# mainSheet.net
KiCad netlist of a schematic drawn in Altium Designer
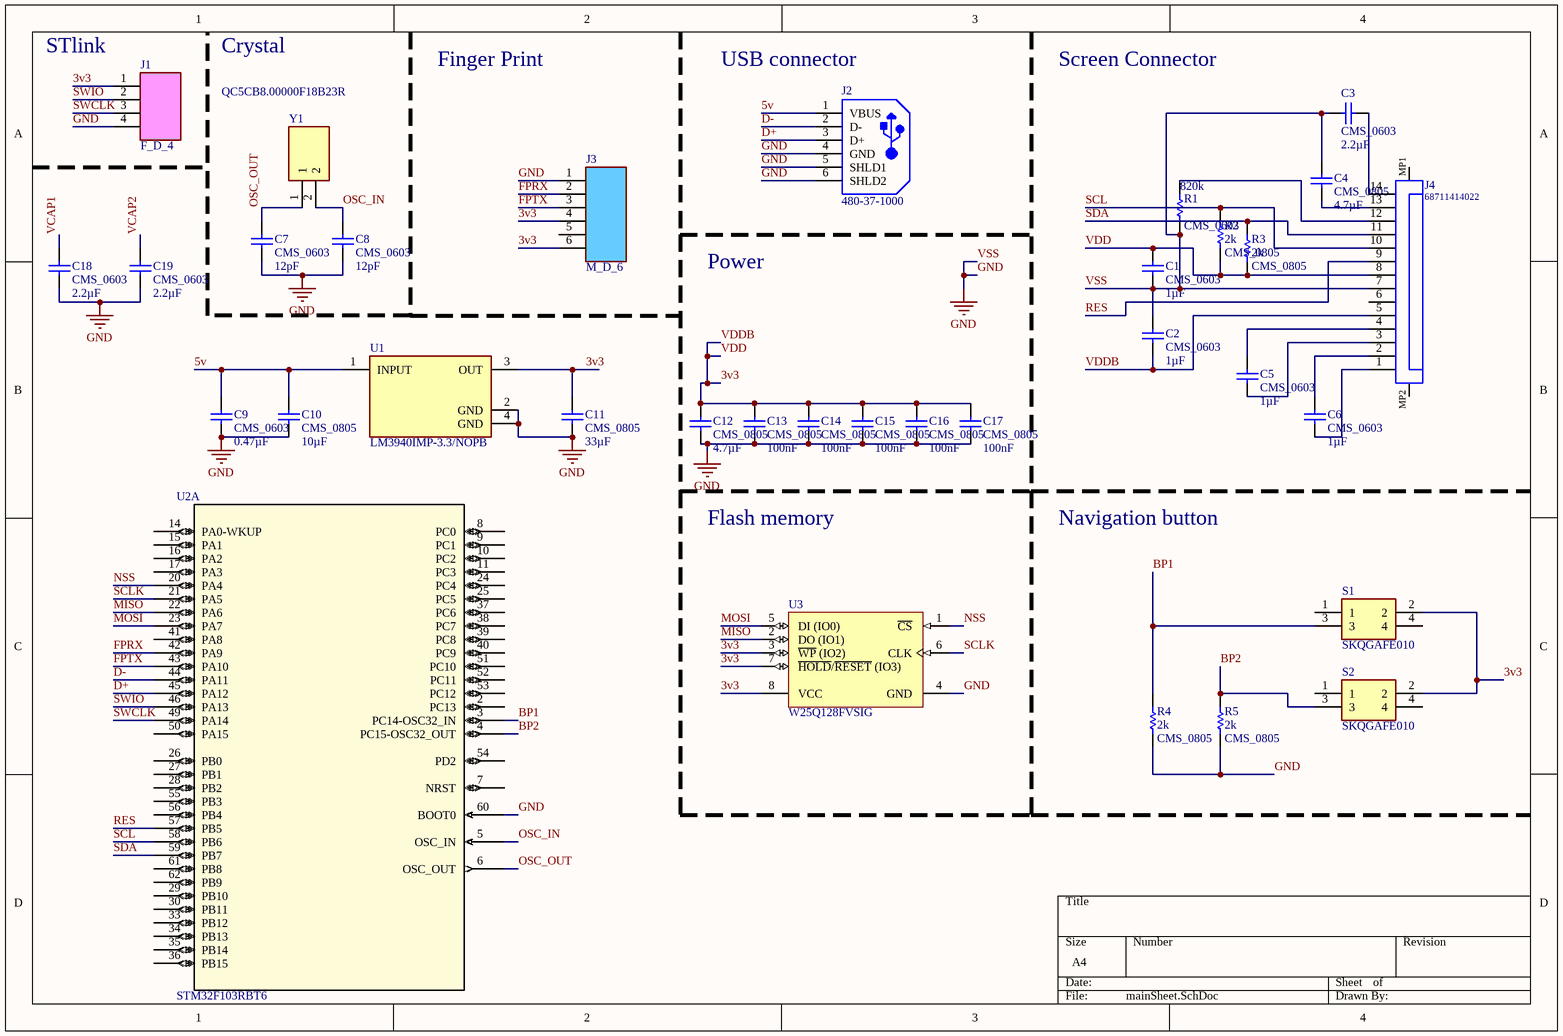
[diagram p0: mainSheet.SchDoc]

(export (version "E")
  (design (tool "Eeschema 10.0.6"))
  (components
    (comp (ref "C1")
      (value "CMS_0603")
      (footprint "CONDENSATEUR_CMS_0603")
      (description "CONDENSATEUR CMS CERAMIQUE 0603")
      (fields (field (name "TYPE") "CMS_0603") (field (name "CONDO") "1µF"))
      (libsource (lib "composants passifs") (part "CONDENSATEUR_CMS_CER_0603"))
    )
    (comp (ref "C2")
      (value "CMS_0603")
      (footprint "CONDENSATEUR_CMS_0603")
      (description "CONDENSATEUR CMS CERAMIQUE 0603")
      (fields (field (name "TYPE") "CMS_0603") (field (name "CONDO") "1µF"))
      (libsource (lib "composants passifs") (part "CONDENSATEUR_CMS_CER_0603"))
    )
    (comp (ref "C3")
      (value "CMS_0603")
      (footprint "CONDENSATEUR_CMS_0603")
      (description "CONDENSATEUR CMS CERAMIQUE 0603")
      (fields (field (name "TYPE") "CMS_0603") (field (name "CONDO") "2.2µF"))
      (libsource (lib "composants passifs") (part "CONDENSATEUR_CMS_CER_0603"))
    )
    (comp (ref "C4")
      (value "CMS_0805")
      (footprint "CONDENSATEUR_CMS_0805")
      (description "CONDENSATEUR CMS CERAMIQUE 0805")
      (fields (field (name "TYPE") "CMS_0805") (field (name "16V / X7R") "4.7µF"))
      (libsource (lib "composants passifs") (part "CONDENSATEUR_CMS_CER_0805"))
    )
    (comp (ref "C5")
      (value "CMS_0603")
      (footprint "CONDENSATEUR_CMS_0603")
      (description "CONDENSATEUR CMS CERAMIQUE 0603")
      (fields (field (name "TYPE") "CMS_0603") (field (name "16V X5R") "1µF"))
      (libsource (lib "composants passifs") (part "CONDENSATEUR_CMS_CER_0603"))
    )
    (comp (ref "C6")
      (value "CMS_0603")
      (footprint "CONDENSATEUR_CMS_0603")
      (description "CONDENSATEUR CMS CERAMIQUE 0603")
      (fields (field (name "TYPE") "CMS_0603") (field (name "16V X5R") "1µF"))
      (libsource (lib "composants passifs") (part "CONDENSATEUR_CMS_CER_0603"))
    )
    (comp (ref "C7")
      (value "CMS_0603")
      (footprint "CONDENSATEUR_CMS_0603")
      (description "CONDENSATEUR CMS CERAMIQUE 0603")
      (fields (field (name "TYPE") "CMS_0603") (field (name "CONDO") "12pF"))
      (libsource (lib "composants passifs") (part "CONDENSATEUR_CMS_CER_0603"))
    )
    (comp (ref "C8")
      (value "CMS_0603")
      (footprint "CONDENSATEUR_CMS_0603")
      (description "CONDENSATEUR CMS CERAMIQUE 0603")
      (fields (field (name "TYPE") "CMS_0603") (field (name "CONDO") "12pF"))
      (libsource (lib "composants passifs") (part "CONDENSATEUR_CMS_CER_0603"))
    )
    (comp (ref "C9")
      (value "CMS_0603")
      (footprint "CONDENSATEUR_CMS_0603")
      (description "CONDENSATEUR CMS CERAMIQUE 0603")
      (fields (field (name "TYPE") "CMS_0603") (field (name "CONDO") "0.47µF"))
      (libsource (lib "composants passifs") (part "CONDENSATEUR_CMS_CER_0603"))
    )
    (comp (ref "C10")
      (value "10µF")
      (footprint "CONDENSATEUR_CMS_0805")
      (description "CONDENSATEUR CMS CERAMIQUE 0805")
      (fields (field (name "TYPE") "CMS_0805") (field (name "Comment") "CMS_0805"))
      (libsource (lib "composants passifs") (part "CONDENSATEUR_CMS_CER_0805"))
    )
    (comp (ref "C11")
      (value "33µF")
      (footprint "CONDENSATEUR_CMS_0805")
      (description "CONDENSATEUR CMS CERAMIQUE 0805")
      (fields (field (name "TYPE") "CMS_0805") (field (name "Comment") "CMS_0805"))
      (libsource (lib "composants passifs") (part "CONDENSATEUR_CMS_CER_0805"))
    )
    (comp (ref "C12")
      (value "CMS_0805")
      (footprint "CONDENSATEUR_CMS_0805")
      (description "CONDENSATEUR CMS CERAMIQUE 0805")
      (fields (field (name "TYPE") "CMS_0805") (field (name "16V / X7R") "4.7µF"))
      (libsource (lib "composants passifs") (part "CONDENSATEUR_CMS_CER_0805"))
    )
    (comp (ref "C13")
      (value "100nF")
      (footprint "CONDENSATEUR_CMS_0805")
      (description "CONDENSATEUR CMS CERAMIQUE 0805")
      (fields (field (name "TYPE") "CMS_0805") (field (name "Comment") "CMS_0805"))
      (libsource (lib "composants passifs") (part "CONDENSATEUR_CMS_CER_0805"))
    )
    (comp (ref "C14")
      (value "100nF")
      (footprint "CONDENSATEUR_CMS_0805")
      (description "CONDENSATEUR CMS CERAMIQUE 0805")
      (fields (field (name "TYPE") "CMS_0805") (field (name "Comment") "CMS_0805"))
      (libsource (lib "composants passifs") (part "CONDENSATEUR_CMS_CER_0805"))
    )
    (comp (ref "C15")
      (value "100nF")
      (footprint "CONDENSATEUR_CMS_0805")
      (description "CONDENSATEUR CMS CERAMIQUE 0805")
      (fields (field (name "TYPE") "CMS_0805") (field (name "Comment") "CMS_0805"))
      (libsource (lib "composants passifs") (part "CONDENSATEUR_CMS_CER_0805"))
    )
    (comp (ref "C16")
      (value "100nF")
      (footprint "CONDENSATEUR_CMS_0805")
      (description "CONDENSATEUR CMS CERAMIQUE 0805")
      (fields (field (name "TYPE") "CMS_0805") (field (name "Comment") "CMS_0805"))
      (libsource (lib "composants passifs") (part "CONDENSATEUR_CMS_CER_0805"))
    )
    (comp (ref "C17")
      (value "100nF")
      (footprint "CONDENSATEUR_CMS_0805")
      (description "CONDENSATEUR CMS CERAMIQUE 0805")
      (fields (field (name "TYPE") "CMS_0805") (field (name "Comment") "CMS_0805"))
      (libsource (lib "composants passifs") (part "CONDENSATEUR_CMS_CER_0805"))
    )
    (comp (ref "C18")
      (value "CMS_0603")
      (footprint "CONDENSATEUR_CMS_0603")
      (description "CONDENSATEUR CMS CERAMIQUE 0603")
      (fields (field (name "TYPE") "CMS_0603") (field (name "CONDO") "2.2µF"))
      (libsource (lib "composants passifs") (part "CONDENSATEUR_CMS_CER_0603"))
    )
    (comp (ref "C19")
      (value "CMS_0603")
      (footprint "CONDENSATEUR_CMS_0603")
      (description "CONDENSATEUR CMS CERAMIQUE 0603")
      (fields (field (name "TYPE") "CMS_0603") (field (name "CONDO") "2.2µF"))
      (libsource (lib "composants passifs") (part "CONDENSATEUR_CMS_CER_0603"))
    )
    (comp (ref "J1")
      (value "BARRETTE_4 CONTACTS_1 RANGEE_FEMELLE_DROITE")
      (footprint "BARRETTE_4_F_D")
      (description "BARRETTE 4 CONTACTS 1 RANGEE FEMELLE DROITE")
      (fields (field (name "TYPE") "F_D_4"))
      (libsource (lib "connecteurs") (part "BARRETTE_4 CONTACTS_1 RANGEE_FEMELLE_DROITE"))
    )
    (comp (ref "J2")
      (value "480-37-1000")
      (footprint "MOLX-480-37-1000_V")
      (fields (field (name "TOLERANCE") "1%"))
      (libsource (lib "Components - 04.06.22 - 23.53") (part "CMP-1676-00005-1"))
    )
    (comp (ref "J3")
      (value "BARRETTE_6 CONTACTS_1 RANGEE_MALE_DROITE")
      (footprint "BARRETTE_6_M_D")
      (description "BARRETTE 6 CONTACTS 1 RANGEE MALE DROITE")
      (fields (field (name "TYPE") "M_D_6"))
      (libsource (lib "connecteurs") (part "BARRETTE_6 CONTACTS_1 RANGEE_MALE_DROITE"))
    )
    (comp (ref "J4")
      (value "68711414022")
      (footprint "68711414022")
      (description "SMT ZIF Connectors WR-FPC, Horizontal, Top Contact, pitch 0.5 mm, 14 pins")
      (fields (field (name "MANUFACTURER") "Wurth Elektronik") (field (name "PUBLISHER") "WurthElektronik"))
      (libsource (lib "Components - 04.06.22 - 18.37") (part "CMP-1502-01553-1"))
    )
    (comp (ref "R1")
      (value "820k")
      (footprint "RESISTANCE_CMS_0603")
      (description "RESISTANCE CMS 0603")
      (fields (field (name "TYPE") "CMS_0603") (field (name "Comment") "RESISTANCE_CMS_0603"))
      (libsource (lib "composants passifs") (part "RESISTANCE_CMS_0603"))
    )
    (comp (ref "R2")
      (value "2k")
      (footprint "RESISTANCE_CMS_0805")
      (description "RESISTANCE CMS 0805")
      (fields (field (name "TYPE") "CMS_0805") (field (name "Comment") "RESISTANCE_CMS_0805"))
      (libsource (lib "composants passifs") (part "RESISTANCE_CMS_0805"))
    )
    (comp (ref "R3")
      (value "2k")
      (footprint "RESISTANCE_CMS_0805")
      (description "RESISTANCE CMS 0805")
      (fields (field (name "TYPE") "CMS_0805") (field (name "Comment") "RESISTANCE_CMS_0805"))
      (libsource (lib "composants passifs") (part "RESISTANCE_CMS_0805"))
    )
    (comp (ref "R4")
      (value "2k")
      (footprint "RESISTANCE_CMS_0805")
      (description "RESISTANCE CMS 0805")
      (fields (field (name "TYPE") "CMS_0805") (field (name "Comment") "RESISTANCE_CMS_0805"))
      (libsource (lib "composants passifs") (part "RESISTANCE_CMS_0805"))
    )
    (comp (ref "R5")
      (value "2k")
      (footprint "RESISTANCE_CMS_0805")
      (description "RESISTANCE CMS 0805")
      (fields (field (name "TYPE") "CMS_0805") (field (name "Comment") "RESISTANCE_CMS_0805"))
      (libsource (lib "composants passifs") (part "RESISTANCE_CMS_0805"))
    )
    (comp (ref "S1")
      (value "SKQGAFE010")
      (footprint "SamacSys:SKQGAKE010")
      (description "Switch")
      (fields (field (name "RS PART NUMBER") "7582060P"))
      (libsource (lib "*") (part "SKQGAFE010"))
    )
    (comp (ref "S2")
      (value "SKQGAFE010")
      (footprint "SamacSys:SKQGAKE010")
      (description "Switch")
      (fields (field (name "RS PART NUMBER") "7582060P"))
      (libsource (lib "*") (part "SKQGAFE010"))
    )
    (comp (ref "U1")
      (value "LM3940IMP-3.3/NOPB")
      (footprint "FP-DCY0004A-IPC_C")
      (description "IC REG LINEAR 3.3V 1A SOT223-4")
      (libsource (lib "Components - 07.06.22 - 09.42") (part "CMP-0062-01788-4"))
    )
    (comp (ref "U2")
      (value "STM32F103RBT6")
      (footprint "LQFP64-10x10mm")
      (description "No Description Available")
      (fields (field (name "COPYRIGHT") "Copyright (C) 2022 Ultra Librarian. All rights reserved."))
      (libsource (lib "STM32F103RBT6") (part "STM32F103RBT6"))
    )
    (comp (ref "U3")
      (value "W25Q128FVSIG")
      (footprint "WINB-SOIC-8_N")
      (fields (field (name "MANUFACTURER") "Winbond"))
      (libsource (lib "Components - 04.06.22 - 23.40") (part "CMP-2000-05005-1"))
    )
    (comp (ref "Y1")
      (value "QC5CB8.00000F18B23R")
      (footprint "SamacSys:QC5CB")
      (description "Crystal or Oscillator")
      (fields (field (name "RS PART NUMBER") "8136093P"))
      (libsource (lib "*") (part "QC5CB8.00000F18B23R"))
    )
  )
  (nets
    (net (code "1") (name "/3v3") (class "Default")
      (node (ref "C1") (pin "2") (pinfunction "2_2") (pintype "passive"))
      (node (ref "C11") (pin "2") (pinfunction "2_2") (pintype "passive"))
      (node (ref "C12") (pin "1") (pinfunction "1_1") (pintype "passive"))
      (node (ref "C13") (pin "2") (pinfunction "2_2") (pintype "passive"))
      (node (ref "C14") (pin "2") (pinfunction "2_2") (pintype "passive"))
      (node (ref "C15") (pin "2") (pinfunction "2_2") (pintype "passive"))
      (node (ref "C16") (pin "2") (pinfunction "2_2") (pintype "passive"))
      (node (ref "C17") (pin "2") (pinfunction "2_2") (pintype "passive"))
      (node (ref "C2") (pin "1") (pinfunction "1_1") (pintype "passive"))
      (node (ref "J1") (pin "1") (pinfunction "1_1") (pintype "passive"))
      (node (ref "J3") (pin "4") (pinfunction "4_4") (pintype "passive"))
      (node (ref "J3") (pin "6") (pinfunction "6_6") (pintype "passive"))
      (node (ref "J4") (pin "5") (pinfunction "5_5") (pintype "passive"))
      (node (ref "J4") (pin "8") (pinfunction "8_8") (pintype "passive"))
      (node (ref "R2") (pin "1") (pinfunction "1_1") (pintype "passive"))
      (node (ref "R3") (pin "1") (pinfunction "1_1") (pintype "passive"))
      (node (ref "S1") (pin "2") (pinfunction "2_2") (pintype "passive"))
      (node (ref "S2") (pin "2") (pinfunction "2_2") (pintype "passive"))
      (node (ref "U1") (pin "3") (pinfunction "OUT_3") (pintype "power_in"))
      (node (ref "U3") (pin "3") (pinfunction "~{WP}_(IO2)_3") (pintype "bidirectional"))
      (node (ref "U3") (pin "7") (pinfunction "~{HOLD}/~{RESET}_(IO3)_7") (pintype "bidirectional"))
      (node (ref "U3") (pin "8") (pinfunction "VCC_8") (pintype "power_in"))
    )
    (net (code "2") (name "/5v") (class "Default")
      (node (ref "C10") (pin "2") (pinfunction "2_2") (pintype "passive"))
      (node (ref "C9") (pin "2") (pinfunction "2_2") (pintype "passive"))
      (node (ref "J2") (pin "1") (pinfunction "VBUS_1") (pintype "passive"))
      (node (ref "U1") (pin "1") (pinfunction "INPUT_1") (pintype "power_in"))
    )
    (net (code "3") (name "/BP1") (class "Default")
      (node (ref "R4") (pin "2") (pinfunction "2_2") (pintype "passive"))
      (node (ref "S1") (pin "3") (pinfunction "3_3") (pintype "passive"))
      (node (ref "U2") (pin "3") (pinfunction "PC14-OSC32_IN_3") (pintype "bidirectional"))
    )
    (net (code "4") (name "/BP2") (class "Default")
      (node (ref "R5") (pin "2") (pinfunction "2_2") (pintype "passive"))
      (node (ref "S2") (pin "3") (pinfunction "3_3") (pintype "passive"))
      (node (ref "U2") (pin "4") (pinfunction "PC15-OSC32_OUT_4") (pintype "bidirectional"))
    )
    (net (code "5") (name "/D+") (class "Default")
      (node (ref "J2") (pin "3") (pinfunction "D+_3") (pintype "passive"))
      (node (ref "U2") (pin "45") (pinfunction "PA12_45") (pintype "bidirectional"))
    )
    (net (code "6") (name "/D-") (class "Default")
      (node (ref "J2") (pin "2") (pinfunction "D-_2") (pintype "passive"))
      (node (ref "U2") (pin "44") (pinfunction "PA11_44") (pintype "bidirectional"))
    )
    (net (code "7") (name "/FPRX") (class "Default")
      (node (ref "J3") (pin "2") (pinfunction "2_2") (pintype "passive"))
      (node (ref "U2") (pin "42") (pinfunction "PA9_42") (pintype "bidirectional"))
    )
    (net (code "8") (name "/FPTX") (class "Default")
      (node (ref "J3") (pin "3") (pinfunction "3_3") (pintype "passive"))
      (node (ref "U2") (pin "43") (pinfunction "PA10_43") (pintype "bidirectional"))
    )
    (net (code "9") (name "/MISO") (class "Default")
      (node (ref "U2") (pin "22") (pinfunction "PA6_22") (pintype "bidirectional"))
      (node (ref "U3") (pin "2") (pinfunction "DO_(IO1)_2") (pintype "bidirectional"))
    )
    (net (code "10") (name "/MOSI") (class "Default")
      (node (ref "U2") (pin "23") (pinfunction "PA7_23") (pintype "bidirectional"))
      (node (ref "U3") (pin "5") (pinfunction "DI_(IO0)_5") (pintype "bidirectional"))
    )
    (net (code "11") (name "/NSS") (class "Default")
      (node (ref "U2") (pin "20") (pinfunction "PA4_20") (pintype "bidirectional"))
      (node (ref "U3") (pin "1") (pinfunction "~{CS}_1") (pintype "input"))
    )
    (net (code "12") (name "/OSC_IN") (class "Default")
      (node (ref "C8") (pin "2") (pinfunction "2_2") (pintype "passive"))
      (node (ref "U2") (pin "5") (pinfunction "OSC_IN_5") (pintype "input"))
      (node (ref "Y1") (pin "2") (pinfunction "2_2") (pintype "passive"))
    )
    (net (code "13") (name "/OSC_OUT") (class "Default")
      (node (ref "C7") (pin "2") (pinfunction "2_2") (pintype "passive"))
      (node (ref "U2") (pin "6") (pinfunction "OSC_OUT_6") (pintype "output"))
      (node (ref "Y1") (pin "1") (pinfunction "1_1") (pintype "passive"))
    )
    (net (code "14") (name "/RES") (class "Default")
      (node (ref "J4") (pin "9") (pinfunction "9_9") (pintype "passive"))
      (node (ref "U2") (pin "57") (pinfunction "PB5_57") (pintype "bidirectional"))
    )
    (net (code "15") (name "/SCL") (class "Default")
      (node (ref "J4") (pin "10") (pinfunction "10_10") (pintype "passive"))
      (node (ref "R2") (pin "2") (pinfunction "2_2") (pintype "passive"))
      (node (ref "U2") (pin "58") (pinfunction "PB6_58") (pintype "bidirectional"))
    )
    (net (code "16") (name "/SCLK") (class "Default")
      (node (ref "U2") (pin "21") (pinfunction "PA5_21") (pintype "bidirectional"))
      (node (ref "U3") (pin "6") (pinfunction "CLK_6") (pintype "input"))
    )
    (net (code "17") (name "/SDA") (class "Default")
      (node (ref "J4") (pin "11") (pinfunction "11_11") (pintype "passive"))
      (node (ref "R3") (pin "2") (pinfunction "2_2") (pintype "passive"))
      (node (ref "U2") (pin "59") (pinfunction "PB7_59") (pintype "bidirectional"))
    )
    (net (code "18") (name "/SWCLK") (class "Default")
      (node (ref "J1") (pin "3") (pinfunction "3_3") (pintype "passive"))
      (node (ref "U2") (pin "49") (pinfunction "PA14_49") (pintype "bidirectional"))
    )
    (net (code "19") (name "/SWIO") (class "Default")
      (node (ref "J1") (pin "2") (pinfunction "2_2") (pintype "passive"))
      (node (ref "U2") (pin "46") (pinfunction "PA13_46") (pintype "bidirectional"))
    )
    (net (code "20") (name "/VCAP1") (class "Default")
      (node (ref "C18") (pin "2") (pinfunction "2_2") (pintype "passive"))
    )
    (net (code "21") (name "/VCAP2") (class "Default")
      (node (ref "C19") (pin "2") (pinfunction "2_2") (pintype "passive"))
    )
    (net (code "22") (name "GND") (class "Default")
      (node (ref "C1") (pin "1") (pinfunction "1_1") (pintype "passive"))
      (node (ref "C10") (pin "1") (pinfunction "1_1") (pintype "passive"))
      (node (ref "C11") (pin "1") (pinfunction "1_1") (pintype "passive"))
      (node (ref "C12") (pin "2") (pinfunction "2_2") (pintype "passive"))
      (node (ref "C13") (pin "1") (pinfunction "1_1") (pintype "passive"))
      (node (ref "C14") (pin "1") (pinfunction "1_1") (pintype "passive"))
      (node (ref "C15") (pin "1") (pinfunction "1_1") (pintype "passive"))
      (node (ref "C16") (pin "1") (pinfunction "1_1") (pintype "passive"))
      (node (ref "C17") (pin "1") (pinfunction "1_1") (pintype "passive"))
      (node (ref "C18") (pin "1") (pinfunction "1_1") (pintype "passive"))
      (node (ref "C19") (pin "1") (pinfunction "1_1") (pintype "passive"))
      (node (ref "C2") (pin "2") (pinfunction "2_2") (pintype "passive"))
      (node (ref "C3") (pin "1") (pinfunction "1_1") (pintype "passive"))
      (node (ref "C4") (pin "2") (pinfunction "2_2") (pintype "passive"))
      (node (ref "C7") (pin "1") (pinfunction "1_1") (pintype "passive"))
      (node (ref "C8") (pin "1") (pinfunction "1_1") (pintype "passive"))
      (node (ref "C9") (pin "1") (pinfunction "1_1") (pintype "passive"))
      (node (ref "J1") (pin "4") (pinfunction "4_4") (pintype "passive"))
      (node (ref "J2") (pin "4") (pinfunction "GND_4") (pintype "passive"))
      (node (ref "J2") (pin "5") (pinfunction "SHLD1_5") (pintype "passive"))
      (node (ref "J2") (pin "6") (pinfunction "SHLD2_6") (pintype "passive"))
      (node (ref "J3") (pin "1") (pinfunction "1_1") (pintype "passive"))
      (node (ref "J4") (pin "7") (pinfunction "7_7") (pintype "passive"))
      (node (ref "R1") (pin "1") (pinfunction "1_1") (pintype "passive"))
      (node (ref "R4") (pin "1") (pinfunction "1_1") (pintype "passive"))
      (node (ref "R5") (pin "1") (pinfunction "1_1") (pintype "passive"))
      (node (ref "U1") (pin "2") (pinfunction "GND_2") (pintype "power_in"))
      (node (ref "U1") (pin "4") (pinfunction "GND_4") (pintype "power_in"))
      (node (ref "U2") (pin "60") (pinfunction "BOOT0_60") (pintype "input"))
      (node (ref "U3") (pin "4") (pinfunction "GND_4") (pintype "power_in"))
    )
    (net (code "23") (name "Net-(C3-Pad2)") (class "Default")
      (node (ref "C3") (pin "2") (pinfunction "2_2") (pintype "passive"))
      (node (ref "J4") (pin "14") (pinfunction "14_14") (pintype "passive"))
    )
    (net (code "24") (name "Net-(C4-Pad1)") (class "Default")
      (node (ref "C4") (pin "1") (pinfunction "1_1") (pintype "passive"))
      (node (ref "J4") (pin "13") (pinfunction "13_13") (pintype "passive"))
    )
    (net (code "25") (name "Net-(C5-Pad1)") (class "Default")
      (node (ref "C5") (pin "1") (pinfunction "1_1") (pintype "passive"))
      (node (ref "J4") (pin "3") (pinfunction "3_3") (pintype "passive"))
    )
    (net (code "26") (name "Net-(C5-Pad2)") (class "Default")
      (node (ref "C5") (pin "2") (pinfunction "2_2") (pintype "passive"))
      (node (ref "J4") (pin "4") (pinfunction "4_4") (pintype "passive"))
    )
    (net (code "27") (name "Net-(C6-Pad1)") (class "Default")
      (node (ref "C6") (pin "1") (pinfunction "1_1") (pintype "passive"))
      (node (ref "J4") (pin "1") (pinfunction "1_1") (pintype "passive"))
    )
    (net (code "28") (name "Net-(C6-Pad2)") (class "Default")
      (node (ref "C6") (pin "2") (pinfunction "2_2") (pintype "passive"))
      (node (ref "J4") (pin "2") (pinfunction "2_2") (pintype "passive"))
    )
    (net (code "29") (name "Net-(J4-Pad12)") (class "Default")
      (node (ref "J4") (pin "12") (pinfunction "12_12") (pintype "passive"))
      (node (ref "R1") (pin "2") (pinfunction "2_2") (pintype "passive"))
    )
    (net (code "30") (name "unconnected-(J3-Pad5)") (class "Default")
      (node (ref "J3") (pin "5") (pinfunction "5_5") (pintype "passive"))
    )
    (net (code "31") (name "unconnected-(J4-Pad6)") (class "Default")
      (node (ref "J4") (pin "6") (pinfunction "6_6") (pintype "passive"))
    )
    (net (code "32") (name "unconnected-(J4-PadMP1)") (class "Default")
      (node (ref "J4") (pin "MP1") (pinfunction "MP1_MP1") (pintype "passive"))
    )
    (net (code "33") (name "unconnected-(J4-PadMP2)") (class "Default")
      (node (ref "J4") (pin "MP2") (pinfunction "MP2_MP2") (pintype "passive"))
    )
    (net (code "34") (name "unconnected-(S1-Pad1)") (class "Default")
      (node (ref "S1") (pin "1") (pinfunction "1_1") (pintype "passive"))
    )
    (net (code "35") (name "unconnected-(S1-Pad4)") (class "Default")
      (node (ref "S1") (pin "4") (pinfunction "4_4") (pintype "passive"))
    )
    (net (code "36") (name "unconnected-(S2-Pad1)") (class "Default")
      (node (ref "S2") (pin "1") (pinfunction "1_1") (pintype "passive"))
    )
    (net (code "37") (name "unconnected-(S2-Pad4)") (class "Default")
      (node (ref "S2") (pin "4") (pinfunction "4_4") (pintype "passive"))
    )
    (net (code "38") (name "unconnected-(U2A-NRST-Pad7)") (class "Default")
      (node (ref "U2") (pin "7") (pinfunction "NRST_7") (pintype "bidirectional"))
    )
    (net (code "39") (name "unconnected-(U2A-PA0-WKUP-Pad14)") (class "Default")
      (node (ref "U2") (pin "14") (pinfunction "PA0-WKUP_14") (pintype "bidirectional"))
    )
    (net (code "40") (name "unconnected-(U2A-PA1-Pad15)") (class "Default")
      (node (ref "U2") (pin "15") (pinfunction "PA1_15") (pintype "bidirectional"))
    )
    (net (code "41") (name "unconnected-(U2A-PA2-Pad16)") (class "Default")
      (node (ref "U2") (pin "16") (pinfunction "PA2_16") (pintype "bidirectional"))
    )
    (net (code "42") (name "unconnected-(U2A-PA3-Pad17)") (class "Default")
      (node (ref "U2") (pin "17") (pinfunction "PA3_17") (pintype "bidirectional"))
    )
    (net (code "43") (name "unconnected-(U2A-PA8-Pad41)") (class "Default")
      (node (ref "U2") (pin "41") (pinfunction "PA8_41") (pintype "bidirectional"))
    )
    (net (code "44") (name "unconnected-(U2A-PA15-Pad50)") (class "Default")
      (node (ref "U2") (pin "50") (pinfunction "PA15_50") (pintype "bidirectional"))
    )
    (net (code "45") (name "unconnected-(U2A-PB0-Pad26)") (class "Default")
      (node (ref "U2") (pin "26") (pinfunction "PB0_26") (pintype "bidirectional"))
    )
    (net (code "46") (name "unconnected-(U2A-PB1-Pad27)") (class "Default")
      (node (ref "U2") (pin "27") (pinfunction "PB1_27") (pintype "bidirectional"))
    )
    (net (code "47") (name "unconnected-(U2A-PB2-Pad28)") (class "Default")
      (node (ref "U2") (pin "28") (pinfunction "PB2_28") (pintype "bidirectional"))
    )
    (net (code "48") (name "unconnected-(U2A-PB3-Pad55)") (class "Default")
      (node (ref "U2") (pin "55") (pinfunction "PB3_55") (pintype "bidirectional"))
    )
    (net (code "49") (name "unconnected-(U2A-PB4-Pad56)") (class "Default")
      (node (ref "U2") (pin "56") (pinfunction "PB4_56") (pintype "bidirectional"))
    )
    (net (code "50") (name "unconnected-(U2A-PB8-Pad61)") (class "Default")
      (node (ref "U2") (pin "61") (pinfunction "PB8_61") (pintype "bidirectional"))
    )
    (net (code "51") (name "unconnected-(U2A-PB9-Pad62)") (class "Default")
      (node (ref "U2") (pin "62") (pinfunction "PB9_62") (pintype "bidirectional"))
    )
    (net (code "52") (name "unconnected-(U2A-PB10-Pad29)") (class "Default")
      (node (ref "U2") (pin "29") (pinfunction "PB10_29") (pintype "bidirectional"))
    )
    (net (code "53") (name "unconnected-(U2A-PB11-Pad30)") (class "Default")
      (node (ref "U2") (pin "30") (pinfunction "PB11_30") (pintype "bidirectional"))
    )
    (net (code "54") (name "unconnected-(U2A-PB12-Pad33)") (class "Default")
      (node (ref "U2") (pin "33") (pinfunction "PB12_33") (pintype "bidirectional"))
    )
    (net (code "55") (name "unconnected-(U2A-PB13-Pad34)") (class "Default")
      (node (ref "U2") (pin "34") (pinfunction "PB13_34") (pintype "bidirectional"))
    )
    (net (code "56") (name "unconnected-(U2A-PB14-Pad35)") (class "Default")
      (node (ref "U2") (pin "35") (pinfunction "PB14_35") (pintype "bidirectional"))
    )
    (net (code "57") (name "unconnected-(U2A-PB15-Pad36)") (class "Default")
      (node (ref "U2") (pin "36") (pinfunction "PB15_36") (pintype "bidirectional"))
    )
    (net (code "58") (name "unconnected-(U2A-PC0-Pad8)") (class "Default")
      (node (ref "U2") (pin "8") (pinfunction "PC0_8") (pintype "bidirectional"))
    )
    (net (code "59") (name "unconnected-(U2A-PC1-Pad9)") (class "Default")
      (node (ref "U2") (pin "9") (pinfunction "PC1_9") (pintype "bidirectional"))
    )
    (net (code "60") (name "unconnected-(U2A-PC2-Pad10)") (class "Default")
      (node (ref "U2") (pin "10") (pinfunction "PC2_10") (pintype "bidirectional"))
    )
    (net (code "61") (name "unconnected-(U2A-PC3-Pad11)") (class "Default")
      (node (ref "U2") (pin "11") (pinfunction "PC3_11") (pintype "bidirectional"))
    )
    (net (code "62") (name "unconnected-(U2A-PC4-Pad24)") (class "Default")
      (node (ref "U2") (pin "24") (pinfunction "PC4_24") (pintype "bidirectional"))
    )
    (net (code "63") (name "unconnected-(U2A-PC5-Pad25)") (class "Default")
      (node (ref "U2") (pin "25") (pinfunction "PC5_25") (pintype "bidirectional"))
    )
    (net (code "64") (name "unconnected-(U2A-PC6-Pad37)") (class "Default")
      (node (ref "U2") (pin "37") (pinfunction "PC6_37") (pintype "bidirectional"))
    )
    (net (code "65") (name "unconnected-(U2A-PC7-Pad38)") (class "Default")
      (node (ref "U2") (pin "38") (pinfunction "PC7_38") (pintype "bidirectional"))
    )
    (net (code "66") (name "unconnected-(U2A-PC8-Pad39)") (class "Default")
      (node (ref "U2") (pin "39") (pinfunction "PC8_39") (pintype "bidirectional"))
    )
    (net (code "67") (name "unconnected-(U2A-PC9-Pad40)") (class "Default")
      (node (ref "U2") (pin "40") (pinfunction "PC9_40") (pintype "bidirectional"))
    )
    (net (code "68") (name "unconnected-(U2A-PC10-Pad51)") (class "Default")
      (node (ref "U2") (pin "51") (pinfunction "PC10_51") (pintype "bidirectional"))
    )
    (net (code "69") (name "unconnected-(U2A-PC11-Pad52)") (class "Default")
      (node (ref "U2") (pin "52") (pinfunction "PC11_52") (pintype "bidirectional"))
    )
    (net (code "70") (name "unconnected-(U2A-PC12-Pad53)") (class "Default")
      (node (ref "U2") (pin "53") (pinfunction "PC12_53") (pintype "bidirectional"))
    )
    (net (code "71") (name "unconnected-(U2A-PC13-Pad2)") (class "Default")
      (node (ref "U2") (pin "2") (pinfunction "PC13_2") (pintype "bidirectional"))
    )
    (net (code "72") (name "unconnected-(U2A-PD2-Pad54)") (class "Default")
      (node (ref "U2") (pin "54") (pinfunction "PD2_54") (pintype "bidirectional"))
    )
  )
)
